# EnvironmentalElements.net
KiCad netlist of a schematic drawn in Altium Designer
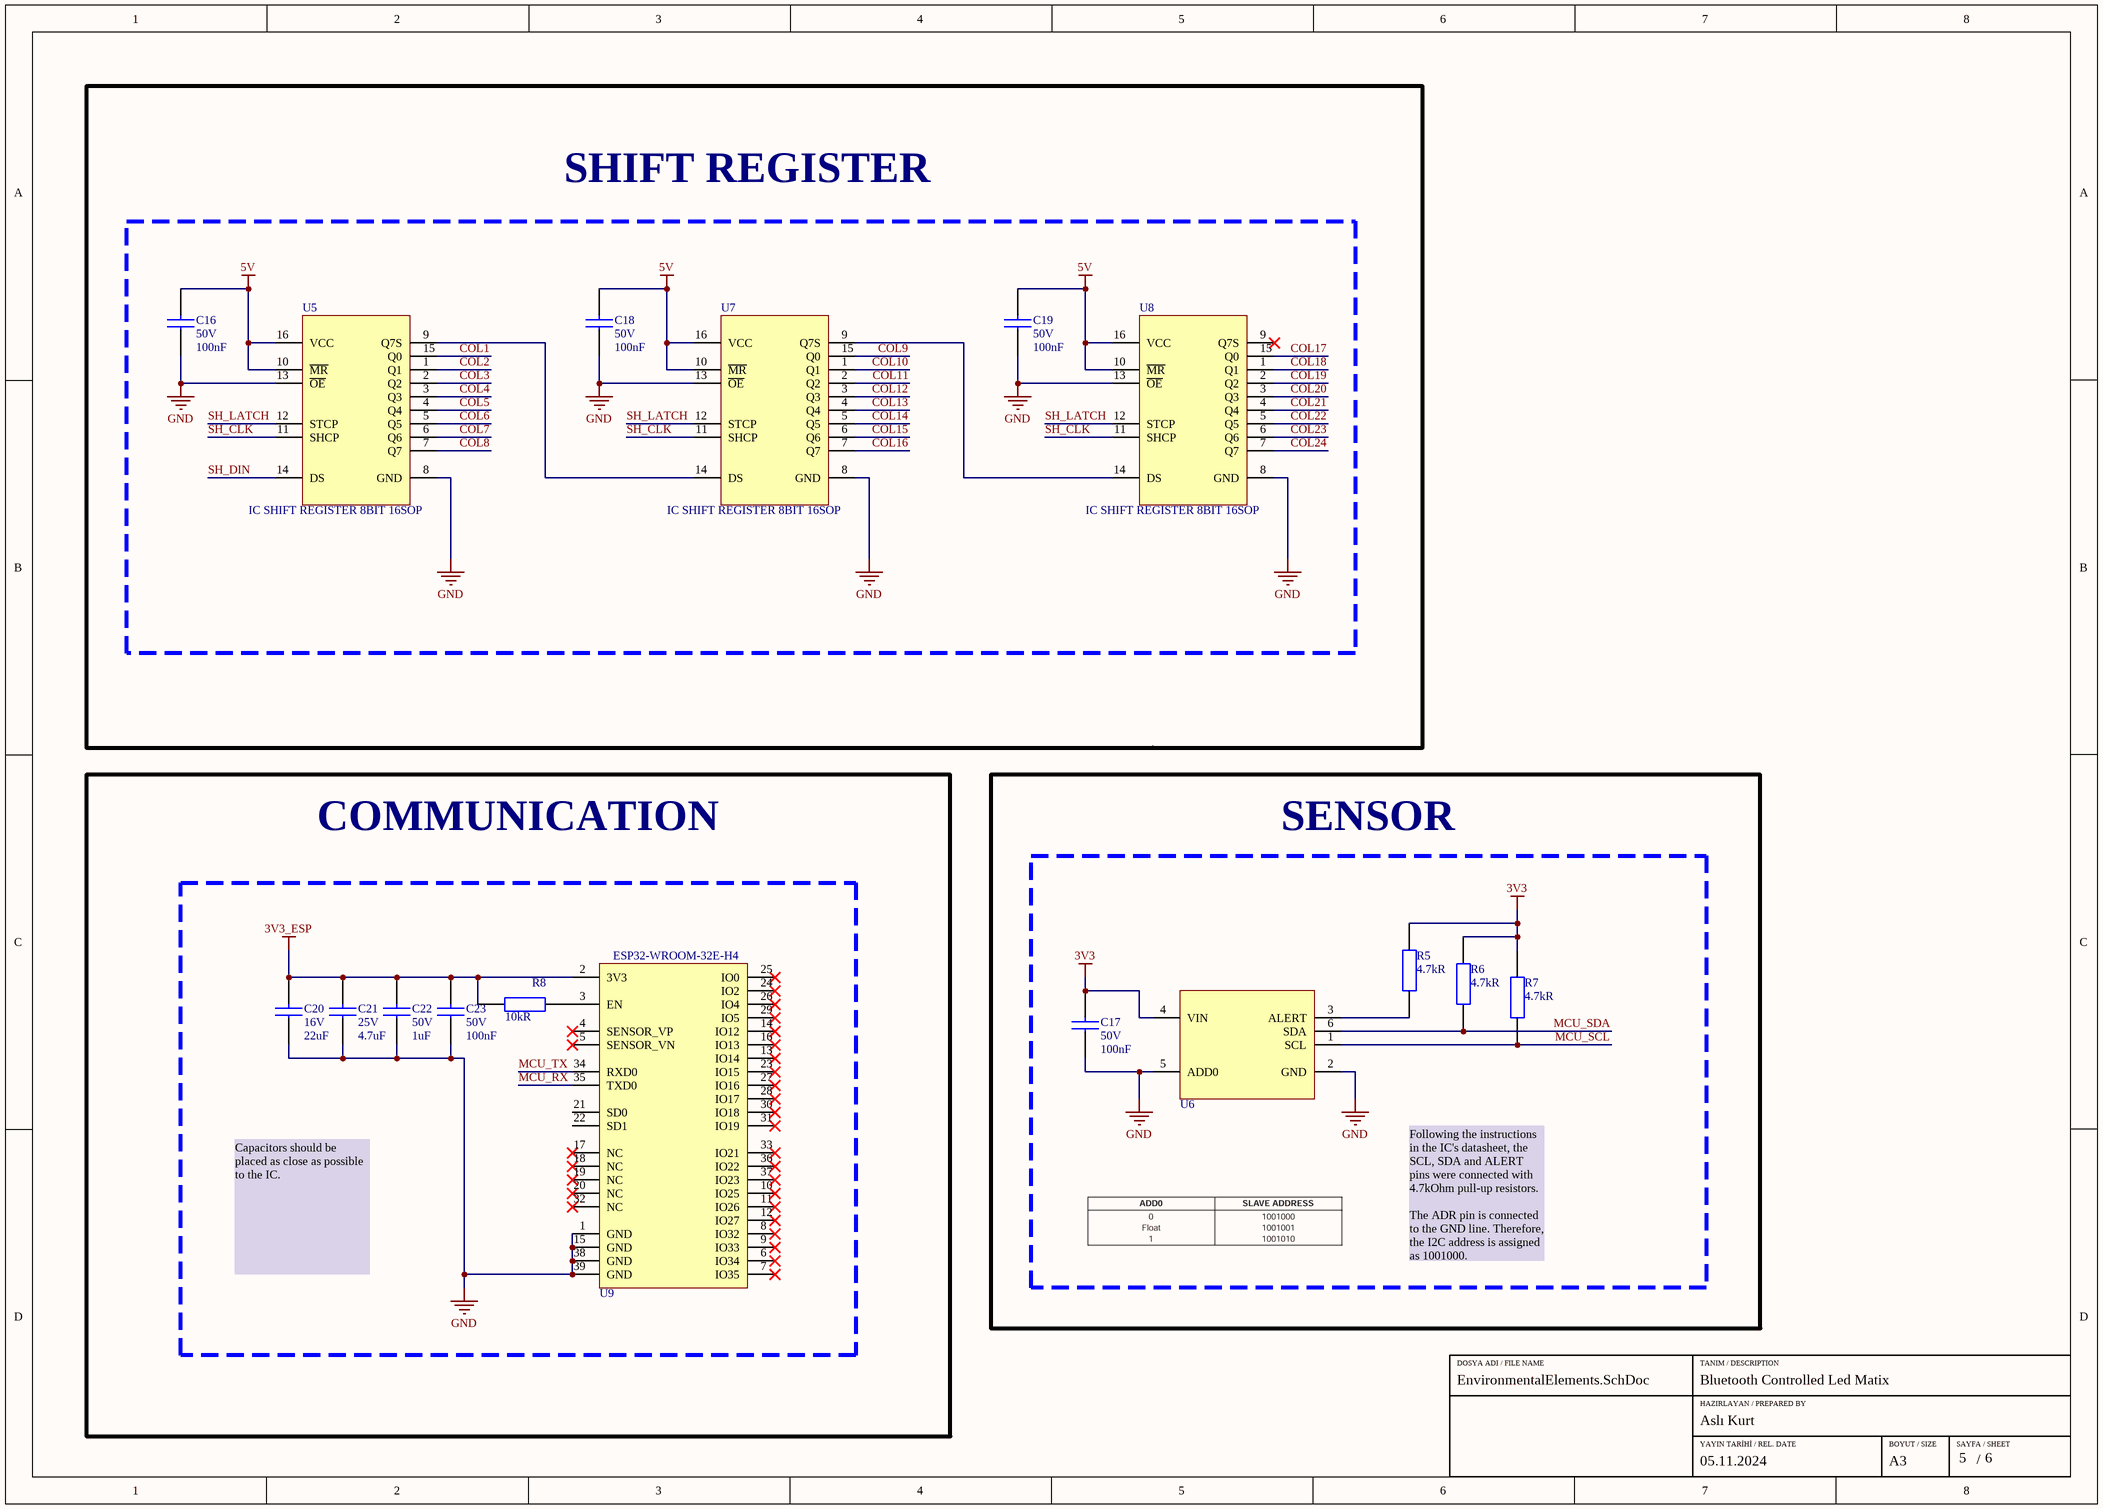
[diagram p0: EnvironmentalElements.SchDoc]

(export (version "E")
  (design (tool "Eeschema 10.0.6"))
  (components
    (comp (ref "C16")
      (value "C0603C104K5RACTU")
      (footprint "CAP_0603")
      (description "CAP CER 100nF %10 0603 SMD")
      (fields
        (field (name "MANUFACTURER") "KEMET")
        (field (name "TOLERANCE") "10%")
        (field (name "VOLTAGE RATING (DC)") "50V")
        (field (name "CAPACITANCE") "100nF")
        (field (name "DESIGNEDBY") "Aslı Kurt")
      )
      (libsource (lib "MyLibrary") (part "CAP CER 100nF 0603"))
    )
    (comp (ref "C17")
      (value "C0603C104K5RACTU")
      (footprint "CAP_0603")
      (description "CAP CER 100nF %10 0603 SMD")
      (fields
        (field (name "MANUFACTURER") "KEMET")
        (field (name "TOLERANCE") "10%")
        (field (name "VOLTAGE RATING (DC)") "50V")
        (field (name "CAPACITANCE") "100nF")
        (field (name "DESIGNEDBY") "Aslı Kurt")
      )
      (libsource (lib "MyLibrary") (part "CAP CER 100nF 0603"))
    )
    (comp (ref "C18")
      (value "C0603C104K5RACTU")
      (footprint "CAP_0603")
      (description "CAP CER 100nF %10 0603 SMD")
      (fields
        (field (name "MANUFACTURER") "KEMET")
        (field (name "TOLERANCE") "10%")
        (field (name "VOLTAGE RATING (DC)") "50V")
        (field (name "CAPACITANCE") "100nF")
        (field (name "DESIGNEDBY") "Aslı Kurt")
      )
      (libsource (lib "MyLibrary") (part "CAP CER 100nF 0603"))
    )
    (comp (ref "C19")
      (value "C0603C104K5RACTU")
      (footprint "CAP_0603")
      (description "CAP CER 100nF %10 0603 SMD")
      (fields
        (field (name "MANUFACTURER") "KEMET")
        (field (name "TOLERANCE") "10%")
        (field (name "VOLTAGE RATING (DC)") "50V")
        (field (name "CAPACITANCE") "100nF")
        (field (name "DESIGNEDBY") "Aslı Kurt")
      )
      (libsource (lib "MyLibrary") (part "CAP CER 100nF 0603"))
    )
    (comp (ref "C20")
      (value "CL10A226MO7JZNC")
      (footprint "CAP_0603")
      (description "Multilayer Ceramic Capacitor, 22 uF, 16 V, ï¿½ 20%, X5R, 0603 [1608 Metric]")
      (fields
        (field (name "MANUFACTURER") "Samsung")
        (field (name "TOLERANCE") "20%")
        (field (name "VOLTAGE RATING") "16V")
        (field (name "CAPACITANCE") "22uF")
        (field (name "DESIGNEDBY") "Aslı Kurt")
      )
      (libsource (lib "MyLibrary") (part "CAP CER 22uF 0603"))
    )
    (comp (ref "C21")
      (value "CL21A475KAQNNNE")
      (footprint "CAP_0805")
      (description "CAP CER 4.7uF %10 0805")
      (fields
        (field (name "MANUFACTURER") "Samsung")
        (field (name "TOLERANCE") "10%")
        (field (name "VOLTAGE RATING") "25V")
        (field (name "CAPACITANCE") "4.7uF")
        (field (name "DESIGNEDBY") "Aslı Kurt")
      )
      (libsource (lib "MyLibrary") (part "CAP CER 4.7uF 0805"))
    )
    (comp (ref "C22")
      (value "CL21B105KBFNNNE")
      (footprint "CAP_0805")
      (description "CAP CER 1uF %10 0805")
      (fields
        (field (name "MANUFACTURER") "Samsung")
        (field (name "TOLERANCE") "10%")
        (field (name "VOLTAGE RATING") "50V")
        (field (name "CAPACITANCE") "1uF")
        (field (name "DESIGNEDBY") "Aslı Kurt")
      )
      (libsource (lib "MyLibrary") (part "CAP CER 1uF 0805"))
    )
    (comp (ref "C23")
      (value "C0603C104K5RACTU")
      (footprint "CAP_0603")
      (description "CAP CER 100nF %10 0603 SMD")
      (fields
        (field (name "MANUFACTURER") "KEMET")
        (field (name "TOLERANCE") "10%")
        (field (name "VOLTAGE RATING (DC)") "50V")
        (field (name "CAPACITANCE") "100nF")
        (field (name "DESIGNEDBY") "Aslı Kurt")
      )
      (libsource (lib "MyLibrary") (part "CAP CER 100nF 0603"))
    )
    (comp (ref "R5")
      (value "RC0805FR-074K7L")
      (footprint "RES_0805")
      (description "RES 4.7K OHM 5% 1/8W 0805")
      (fields
        (field (name "MANUFACTURER") "Yageo")
        (field (name "TOLERANCE") "1%")
        (field (name "RESISTANCE") "4.7kR")
        (field (name "DESIGNEDBY") "Aslı Kurt")
      )
      (libsource (lib "MyLibrary") (part "RES 4.7K OHM 0805 1/8W"))
    )
    (comp (ref "R6")
      (value "RC0805FR-074K7L")
      (footprint "RES_0805")
      (description "RES 4.7K OHM 5% 1/8W 0805")
      (fields
        (field (name "MANUFACTURER") "Yageo")
        (field (name "TOLERANCE") "1%")
        (field (name "RESISTANCE") "4.7kR")
        (field (name "DESIGNEDBY") "Aslı Kurt")
      )
      (libsource (lib "MyLibrary") (part "RES 4.7K OHM 0805 1/8W"))
    )
    (comp (ref "R7")
      (value "RC0805FR-074K7L")
      (footprint "RES_0805")
      (description "RES 4.7K OHM 5% 1/8W 0805")
      (fields
        (field (name "MANUFACTURER") "Yageo")
        (field (name "TOLERANCE") "1%")
        (field (name "RESISTANCE") "4.7kR")
        (field (name "DESIGNEDBY") "Aslı Kurt")
      )
      (libsource (lib "MyLibrary") (part "RES 4.7K OHM 0805 1/8W"))
    )
    (comp (ref "R8")
      (value "RC0805JR-0710KL")
      (footprint "RES_0805")
      (description "RES 10K OHM 5% 1/8W 0805")
      (fields
        (field (name "MANUFACTURER") "Yageo")
        (field (name "TOLERANCE") "5%")
        (field (name "RESISTANCE") "10kR")
        (field (name "DESIGNEDBY") "Aslı Kurt")
      )
      (libsource (lib "MyLibrary") (part "RES 10K OHM 08051/8W"))
    )
    (comp (ref "U5")
      (value "IC SHIFT REGISTER 8BIT 16SOP")
      (footprint "16-SOIC")
      (description "74HC Series 6 V 3-State Surface Mount Shift Register - SOIC-16")
      (fields
        (field (name "MANUFACTURER") "Nexperia")
        (field (name "MANUFACTURER PART NUMBER") "74HC595D,118")
        (field (name "DESIGNEDBY") "Aslı Kurt")
      )
      (libsource (lib "MyLibrary") (part "74HC595D"))
    )
    (comp (ref "U6")
      (value "TMP101NA/3K")
      (footprint "SOT-23-6")
      (description "±2°C Digital temperature sensor with I2C/SMBus interface and alert in SOT-23 6-SOT-23 -55 to 125")
      (fields (field (name "MANUFACTURER") "Texas Instruments") (field (name "DESIGNEDBY") "Aslı Kurt"))
      (libsource (lib "MyLibrary") (part "TMP101NA/3K"))
    )
    (comp (ref "U7")
      (value "IC SHIFT REGISTER 8BIT 16SOP")
      (footprint "16-SOIC")
      (description "74HC Series 6 V 3-State Surface Mount Shift Register - SOIC-16")
      (fields
        (field (name "MANUFACTURER") "Nexperia")
        (field (name "MANUFACTURER PART NUMBER") "74HC595D,118")
        (field (name "DESIGNEDBY") "Aslı Kurt")
      )
      (libsource (lib "MyLibrary") (part "74HC595D"))
    )
    (comp (ref "U8")
      (value "IC SHIFT REGISTER 8BIT 16SOP")
      (footprint "16-SOIC")
      (description "74HC Series 6 V 3-State Surface Mount Shift Register - SOIC-16")
      (fields
        (field (name "MANUFACTURER") "Nexperia")
        (field (name "MANUFACTURER PART NUMBER") "74HC595D,118")
        (field (name "DESIGNEDBY") "Aslı Kurt")
      )
      (libsource (lib "MyLibrary") (part "74HC595D"))
    )
    (comp (ref "U9")
      (value "ESP32-WROOM-32E-H4")
      (footprint "ESP32-WROOM-32E-H4")
      (description "Rf Txrx Module Bt Trace Ant SMD")
      (fields (field (name "MANUFACTURER") "Espressif Systems"))
      (libsource (lib "MyLibrary") (part "ESP32-WROOM-32E-H4"))
    )
  )
  (nets
    (net (code "1") (name "/COL1") (class "Default")
      (node (ref "U5") (pin "15") (pinfunction "Q0_15") (pintype "passive"))
    )
    (net (code "2") (name "/COL2") (class "Default")
      (node (ref "U5") (pin "1") (pinfunction "Q1_1") (pintype "passive"))
    )
    (net (code "3") (name "/COL3") (class "Default")
      (node (ref "U5") (pin "2") (pinfunction "Q2_2") (pintype "passive"))
    )
    (net (code "4") (name "/COL4") (class "Default")
      (node (ref "U5") (pin "3") (pinfunction "Q3_3") (pintype "passive"))
    )
    (net (code "5") (name "/COL5") (class "Default")
      (node (ref "U5") (pin "4") (pinfunction "Q4_4") (pintype "passive"))
    )
    (net (code "6") (name "/COL6") (class "Default")
      (node (ref "U5") (pin "5") (pinfunction "Q5_5") (pintype "passive"))
    )
    (net (code "7") (name "/COL7") (class "Default")
      (node (ref "U5") (pin "6") (pinfunction "Q6_6") (pintype "passive"))
    )
    (net (code "8") (name "/COL8") (class "Default")
      (node (ref "U5") (pin "7") (pinfunction "Q7_7") (pintype "passive"))
    )
    (net (code "9") (name "/COL9") (class "Default")
      (node (ref "U7") (pin "15") (pinfunction "Q0_15") (pintype "passive"))
    )
    (net (code "10") (name "/COL10") (class "Default")
      (node (ref "U7") (pin "1") (pinfunction "Q1_1") (pintype "passive"))
    )
    (net (code "11") (name "/COL11") (class "Default")
      (node (ref "U7") (pin "2") (pinfunction "Q2_2") (pintype "passive"))
    )
    (net (code "12") (name "/COL12") (class "Default")
      (node (ref "U7") (pin "3") (pinfunction "Q3_3") (pintype "passive"))
    )
    (net (code "13") (name "/COL13") (class "Default")
      (node (ref "U7") (pin "4") (pinfunction "Q4_4") (pintype "passive"))
    )
    (net (code "14") (name "/COL14") (class "Default")
      (node (ref "U7") (pin "5") (pinfunction "Q5_5") (pintype "passive"))
    )
    (net (code "15") (name "/COL15") (class "Default")
      (node (ref "U7") (pin "6") (pinfunction "Q6_6") (pintype "passive"))
    )
    (net (code "16") (name "/COL16") (class "Default")
      (node (ref "U7") (pin "7") (pinfunction "Q7_7") (pintype "passive"))
    )
    (net (code "17") (name "/COL17") (class "Default")
      (node (ref "U8") (pin "15") (pinfunction "Q0_15") (pintype "passive"))
    )
    (net (code "18") (name "/COL18") (class "Default")
      (node (ref "U8") (pin "1") (pinfunction "Q1_1") (pintype "passive"))
    )
    (net (code "19") (name "/COL19") (class "Default")
      (node (ref "U8") (pin "2") (pinfunction "Q2_2") (pintype "passive"))
    )
    (net (code "20") (name "/COL20") (class "Default")
      (node (ref "U8") (pin "3") (pinfunction "Q3_3") (pintype "passive"))
    )
    (net (code "21") (name "/COL21") (class "Default")
      (node (ref "U8") (pin "4") (pinfunction "Q4_4") (pintype "passive"))
    )
    (net (code "22") (name "/COL22") (class "Default")
      (node (ref "U8") (pin "5") (pinfunction "Q5_5") (pintype "passive"))
    )
    (net (code "23") (name "/COL23") (class "Default")
      (node (ref "U8") (pin "6") (pinfunction "Q6_6") (pintype "passive"))
    )
    (net (code "24") (name "/COL24") (class "Default")
      (node (ref "U8") (pin "7") (pinfunction "Q7_7") (pintype "passive"))
    )
    (net (code "25") (name "/MCU_RX") (class "Default")
      (node (ref "U9") (pin "35") (pinfunction "TXD0_35") (pintype "passive"))
    )
    (net (code "26") (name "/MCU_SCL") (class "Default")
      (node (ref "R7") (pin "1") (pinfunction "1_1") (pintype "passive"))
      (node (ref "U6") (pin "1") (pinfunction "SCL_1") (pintype "passive"))
    )
    (net (code "27") (name "/MCU_SDA") (class "Default")
      (node (ref "R6") (pin "1") (pinfunction "1_1") (pintype "passive"))
      (node (ref "U6") (pin "6") (pinfunction "SDA_6") (pintype "passive"))
    )
    (net (code "28") (name "/MCU_TX") (class "Default")
      (node (ref "U9") (pin "34") (pinfunction "RXD0_34") (pintype "passive"))
    )
    (net (code "29") (name "/SH_CLK") (class "Default")
      (node (ref "U5") (pin "11") (pinfunction "SHCP_11") (pintype "passive"))
      (node (ref "U7") (pin "11") (pinfunction "SHCP_11") (pintype "passive"))
      (node (ref "U8") (pin "11") (pinfunction "SHCP_11") (pintype "passive"))
    )
    (net (code "30") (name "/SH_DIN") (class "Default")
      (node (ref "U5") (pin "14") (pinfunction "DS_14") (pintype "passive"))
    )
    (net (code "31") (name "/SH_LATCH") (class "Default")
      (node (ref "U5") (pin "12") (pinfunction "STCP_12") (pintype "passive"))
      (node (ref "U7") (pin "12") (pinfunction "STCP_12") (pintype "passive"))
      (node (ref "U8") (pin "12") (pinfunction "STCP_12") (pintype "passive"))
    )
    (net (code "32") (name "3V3") (class "Default")
      (node (ref "C17") (pin "2") (pinfunction "2_2") (pintype "passive"))
      (node (ref "R5") (pin "2") (pinfunction "2_2") (pintype "passive"))
      (node (ref "R6") (pin "2") (pinfunction "2_2") (pintype "passive"))
      (node (ref "R7") (pin "2") (pinfunction "2_2") (pintype "passive"))
      (node (ref "U6") (pin "4") (pinfunction "VIN_4") (pintype "passive"))
    )
    (net (code "33") (name "3V3_ESP") (class "Default")
      (node (ref "C20") (pin "2") (pinfunction "2_2") (pintype "passive"))
      (node (ref "C21") (pin "2") (pinfunction "2_2") (pintype "passive"))
      (node (ref "C22") (pin "2") (pinfunction "2_2") (pintype "passive"))
      (node (ref "C23") (pin "2") (pinfunction "2_2") (pintype "passive"))
      (node (ref "R8") (pin "1") (pinfunction "1_1") (pintype "passive"))
      (node (ref "U9") (pin "2") (pinfunction "3V3_2") (pintype "passive"))
    )
    (net (code "34") (name "5V") (class "Default")
      (node (ref "C16") (pin "2") (pinfunction "2_2") (pintype "passive"))
      (node (ref "C18") (pin "2") (pinfunction "2_2") (pintype "passive"))
      (node (ref "C19") (pin "2") (pinfunction "2_2") (pintype "passive"))
      (node (ref "U5") (pin "10") (pinfunction "~{MR}_10") (pintype "passive"))
      (node (ref "U5") (pin "16") (pinfunction "VCC_16") (pintype "passive"))
      (node (ref "U7") (pin "10") (pinfunction "~{MR}_10") (pintype "passive"))
      (node (ref "U7") (pin "16") (pinfunction "VCC_16") (pintype "passive"))
      (node (ref "U8") (pin "10") (pinfunction "~{MR}_10") (pintype "passive"))
      (node (ref "U8") (pin "16") (pinfunction "VCC_16") (pintype "passive"))
    )
    (net (code "35") (name "GND") (class "Default")
      (node (ref "C16") (pin "1") (pinfunction "1_1") (pintype "passive"))
      (node (ref "C17") (pin "1") (pinfunction "1_1") (pintype "passive"))
      (node (ref "C18") (pin "1") (pinfunction "1_1") (pintype "passive"))
      (node (ref "C19") (pin "1") (pinfunction "1_1") (pintype "passive"))
      (node (ref "C20") (pin "1") (pinfunction "1_1") (pintype "passive"))
      (node (ref "C21") (pin "1") (pinfunction "1_1") (pintype "passive"))
      (node (ref "C22") (pin "1") (pinfunction "1_1") (pintype "passive"))
      (node (ref "C23") (pin "1") (pinfunction "1_1") (pintype "passive"))
      (node (ref "U5") (pin "13") (pinfunction "~{OE}_13") (pintype "passive"))
      (node (ref "U5") (pin "8") (pinfunction "GND_8") (pintype "passive"))
      (node (ref "U6") (pin "2") (pinfunction "GND_2") (pintype "passive"))
      (node (ref "U6") (pin "5") (pinfunction "ADD0_5") (pintype "passive"))
      (node (ref "U7") (pin "13") (pinfunction "~{OE}_13") (pintype "passive"))
      (node (ref "U7") (pin "8") (pinfunction "GND_8") (pintype "passive"))
      (node (ref "U8") (pin "13") (pinfunction "~{OE}_13") (pintype "passive"))
      (node (ref "U8") (pin "8") (pinfunction "GND_8") (pintype "passive"))
      (node (ref "U9") (pin "1") (pinfunction "GND_1") (pintype "passive"))
      (node (ref "U9") (pin "15") (pinfunction "GND_15") (pintype "passive"))
      (node (ref "U9") (pin "38") (pinfunction "GND_38") (pintype "passive"))
      (node (ref "U9") (pin "39") (pinfunction "GND_39") (pintype "passive"))
    )
    (net (code "36") (name "Net-(U5-Q7S)") (class "Default")
      (node (ref "U5") (pin "9") (pinfunction "Q7S_9") (pintype "passive"))
      (node (ref "U7") (pin "14") (pinfunction "DS_14") (pintype "passive"))
    )
    (net (code "37") (name "Net-(U6-ALERT)") (class "Default")
      (node (ref "R5") (pin "1") (pinfunction "1_1") (pintype "passive"))
      (node (ref "U6") (pin "3") (pinfunction "ALERT_3") (pintype "passive"))
    )
    (net (code "38") (name "Net-(U7-Q7S)") (class "Default")
      (node (ref "U7") (pin "9") (pinfunction "Q7S_9") (pintype "passive"))
      (node (ref "U8") (pin "14") (pinfunction "DS_14") (pintype "passive"))
    )
    (net (code "39") (name "Net-(U9-EN)") (class "Default")
      (node (ref "R8") (pin "2") (pinfunction "2_2") (pintype "passive"))
      (node (ref "U9") (pin "3") (pinfunction "EN_3") (pintype "passive"))
    )
    (net (code "40") (name "unconnected-(U8-Q7S-Pad9)") (class "Default")
      (node (ref "U8") (pin "9") (pinfunction "Q7S_9") (pintype "passive+no_connect"))
    )
    (net (code "41") (name "unconnected-(U9-IO0-Pad25)") (class "Default")
      (node (ref "U9") (pin "25") (pinfunction "IO0_25") (pintype "passive+no_connect"))
    )
    (net (code "42") (name "unconnected-(U9-IO2-Pad24)") (class "Default")
      (node (ref "U9") (pin "24") (pinfunction "IO2_24") (pintype "passive+no_connect"))
    )
    (net (code "43") (name "unconnected-(U9-IO4-Pad26)") (class "Default")
      (node (ref "U9") (pin "26") (pinfunction "IO4_26") (pintype "passive+no_connect"))
    )
    (net (code "44") (name "unconnected-(U9-IO5-Pad29)") (class "Default")
      (node (ref "U9") (pin "29") (pinfunction "IO5_29") (pintype "passive+no_connect"))
    )
    (net (code "45") (name "unconnected-(U9-IO12-Pad14)") (class "Default")
      (node (ref "U9") (pin "14") (pinfunction "IO12_14") (pintype "passive+no_connect"))
    )
    (net (code "46") (name "unconnected-(U9-IO13-Pad16)") (class "Default")
      (node (ref "U9") (pin "16") (pinfunction "IO13_16") (pintype "passive+no_connect"))
    )
    (net (code "47") (name "unconnected-(U9-IO14-Pad13)") (class "Default")
      (node (ref "U9") (pin "13") (pinfunction "IO14_13") (pintype "passive+no_connect"))
    )
    (net (code "48") (name "unconnected-(U9-IO15-Pad23)") (class "Default")
      (node (ref "U9") (pin "23") (pinfunction "IO15_23") (pintype "passive+no_connect"))
    )
    (net (code "49") (name "unconnected-(U9-IO16-Pad27)") (class "Default")
      (node (ref "U9") (pin "27") (pinfunction "IO16_27") (pintype "passive+no_connect"))
    )
    (net (code "50") (name "unconnected-(U9-IO17-Pad28)") (class "Default")
      (node (ref "U9") (pin "28") (pinfunction "IO17_28") (pintype "passive+no_connect"))
    )
    (net (code "51") (name "unconnected-(U9-IO18-Pad30)") (class "Default")
      (node (ref "U9") (pin "30") (pinfunction "IO18_30") (pintype "passive+no_connect"))
    )
    (net (code "52") (name "unconnected-(U9-IO19-Pad31)") (class "Default")
      (node (ref "U9") (pin "31") (pinfunction "IO19_31") (pintype "passive+no_connect"))
    )
    (net (code "53") (name "unconnected-(U9-IO21-Pad33)") (class "Default")
      (node (ref "U9") (pin "33") (pinfunction "IO21_33") (pintype "passive+no_connect"))
    )
    (net (code "54") (name "unconnected-(U9-IO22-Pad36)") (class "Default")
      (node (ref "U9") (pin "36") (pinfunction "IO22_36") (pintype "passive+no_connect"))
    )
    (net (code "55") (name "unconnected-(U9-IO23-Pad37)") (class "Default")
      (node (ref "U9") (pin "37") (pinfunction "IO23_37") (pintype "passive+no_connect"))
    )
    (net (code "56") (name "unconnected-(U9-IO25-Pad10)") (class "Default")
      (node (ref "U9") (pin "10") (pinfunction "IO25_10") (pintype "passive+no_connect"))
    )
    (net (code "57") (name "unconnected-(U9-IO26-Pad11)") (class "Default")
      (node (ref "U9") (pin "11") (pinfunction "IO26_11") (pintype "passive+no_connect"))
    )
    (net (code "58") (name "unconnected-(U9-IO27-Pad12)") (class "Default")
      (node (ref "U9") (pin "12") (pinfunction "IO27_12") (pintype "passive+no_connect"))
    )
    (net (code "59") (name "unconnected-(U9-IO32-Pad8)") (class "Default")
      (node (ref "U9") (pin "8") (pinfunction "IO32_8") (pintype "passive+no_connect"))
    )
    (net (code "60") (name "unconnected-(U9-IO33-Pad9)") (class "Default")
      (node (ref "U9") (pin "9") (pinfunction "IO33_9") (pintype "passive+no_connect"))
    )
    (net (code "61") (name "unconnected-(U9-IO34-Pad6)") (class "Default")
      (node (ref "U9") (pin "6") (pinfunction "IO34_6") (pintype "passive+no_connect"))
    )
    (net (code "62") (name "unconnected-(U9-IO35-Pad7)") (class "Default")
      (node (ref "U9") (pin "7") (pinfunction "IO35_7") (pintype "passive+no_connect"))
    )
    (net (code "63") (name "unconnected-(U9-NC-Pad17)") (class "Default")
      (node (ref "U9") (pin "17") (pinfunction "NC_17") (pintype "passive+no_connect"))
    )
    (net (code "64") (name "unconnected-(U9-NC-Pad18)") (class "Default")
      (node (ref "U9") (pin "18") (pinfunction "NC_18") (pintype "passive+no_connect"))
    )
    (net (code "65") (name "unconnected-(U9-NC-Pad19)") (class "Default")
      (node (ref "U9") (pin "19") (pinfunction "NC_19") (pintype "passive+no_connect"))
    )
    (net (code "66") (name "unconnected-(U9-NC-Pad20)") (class "Default")
      (node (ref "U9") (pin "20") (pinfunction "NC_20") (pintype "passive+no_connect"))
    )
    (net (code "67") (name "unconnected-(U9-NC-Pad32)") (class "Default")
      (node (ref "U9") (pin "32") (pinfunction "NC_32") (pintype "passive+no_connect"))
    )
    (net (code "68") (name "unconnected-(U9-SD0-Pad21)") (class "Default")
      (node (ref "U9") (pin "21") (pinfunction "SD0_21") (pintype "passive"))
    )
    (net (code "69") (name "unconnected-(U9-SD1-Pad22)") (class "Default")
      (node (ref "U9") (pin "22") (pinfunction "SD1_22") (pintype "passive"))
    )
    (net (code "70") (name "unconnected-(U9-SENSOR_VN-Pad5)") (class "Default")
      (node (ref "U9") (pin "5") (pinfunction "SENSOR_VN_5") (pintype "passive+no_connect"))
    )
    (net (code "71") (name "unconnected-(U9-SENSOR_VP-Pad4)") (class "Default")
      (node (ref "U9") (pin "4") (pinfunction "SENSOR_VP_4") (pintype "passive+no_connect"))
    )
  )
)
